# base.net
KiCad netlist of a schematic drawn in EAGLE
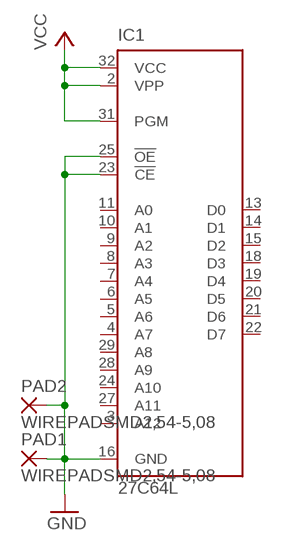
[diagram p0: schematic, sheet 1]

(export (version "E")
  (design (tool "Eeschema 10.0.6"))
  (components
    (comp (ref "IC1")
      (value "27C64L")
      (footprint "eagle-import:PLCC-32")
      (libsource (lib "eagle-import") (part "2764LC"))
    )
    (comp (ref "PAD1")
      (value "WIREPADSMD2,54-5,08")
      (footprint "eagle-import:SMD2,54-5,08")
      (libsource (lib "eagle-import") (part "WIREPADSMD2,54-5,08"))
    )
    (comp (ref "PAD2")
      (value "WIREPADSMD2,54-5,08")
      (footprint "eagle-import:SMD2,54-5,08")
      (libsource (lib "eagle-import") (part "WIREPADSMD2,54-5,08"))
    )
  )
  (nets
    (net (code "1") (name "GND") (class "Default")
      (node (ref "IC1") (pin "16") (pinfunction "GND_16") (pintype "power_in"))
      (node (ref "IC1") (pin "23") (pinfunction "~{CE}_23") (pintype "input"))
      (node (ref "IC1") (pin "25") (pinfunction "~{OE}_25") (pintype "input"))
      (node (ref "PAD1") (pin "1") (pinfunction "P_1") (pintype "passive"))
      (node (ref "PAD2") (pin "1") (pinfunction "P_1") (pintype "passive"))
    )
    (net (code "2") (name "VCC") (class "Default")
      (node (ref "IC1") (pin "2") (pinfunction "VPP_2") (pintype "input"))
      (node (ref "IC1") (pin "31") (pinfunction "PGM_31") (pintype "input"))
      (node (ref "IC1") (pin "32") (pinfunction "VCC_32") (pintype "power_in"))
    )
    (net (code "3") (name "unconnected-(IC1-A0-Pad11)") (class "Default")
      (node (ref "IC1") (pin "11") (pinfunction "A0_11") (pintype "input"))
    )
    (net (code "4") (name "unconnected-(IC1-A1-Pad10)") (class "Default")
      (node (ref "IC1") (pin "10") (pinfunction "A1_10") (pintype "input"))
    )
    (net (code "5") (name "unconnected-(IC1-A2-Pad9)") (class "Default")
      (node (ref "IC1") (pin "9") (pinfunction "A2_9") (pintype "input"))
    )
    (net (code "6") (name "unconnected-(IC1-A3-Pad8)") (class "Default")
      (node (ref "IC1") (pin "8") (pinfunction "A3_8") (pintype "input"))
    )
    (net (code "7") (name "unconnected-(IC1-A4-Pad7)") (class "Default")
      (node (ref "IC1") (pin "7") (pinfunction "A4_7") (pintype "input"))
    )
    (net (code "8") (name "unconnected-(IC1-A5-Pad6)") (class "Default")
      (node (ref "IC1") (pin "6") (pinfunction "A5_6") (pintype "input"))
    )
    (net (code "9") (name "unconnected-(IC1-A6-Pad5)") (class "Default")
      (node (ref "IC1") (pin "5") (pinfunction "A6_5") (pintype "input"))
    )
    (net (code "10") (name "unconnected-(IC1-A7-Pad4)") (class "Default")
      (node (ref "IC1") (pin "4") (pinfunction "A7_4") (pintype "input"))
    )
    (net (code "11") (name "unconnected-(IC1-A8-Pad29)") (class "Default")
      (node (ref "IC1") (pin "29") (pinfunction "A8_29") (pintype "input"))
    )
    (net (code "12") (name "unconnected-(IC1-A9-Pad28)") (class "Default")
      (node (ref "IC1") (pin "28") (pinfunction "A9_28") (pintype "input"))
    )
    (net (code "13") (name "unconnected-(IC1-A10-Pad24)") (class "Default")
      (node (ref "IC1") (pin "24") (pinfunction "A10_24") (pintype "input"))
    )
    (net (code "14") (name "unconnected-(IC1-A11-Pad27)") (class "Default")
      (node (ref "IC1") (pin "27") (pinfunction "A11_27") (pintype "input"))
    )
    (net (code "15") (name "unconnected-(IC1-A12-Pad3)") (class "Default")
      (node (ref "IC1") (pin "3") (pinfunction "A12_3") (pintype "input"))
    )
    (net (code "16") (name "unconnected-(IC1-D0-Pad13)") (class "Default")
      (node (ref "IC1") (pin "13") (pinfunction "D0_13") (pintype "tri_state"))
    )
    (net (code "17") (name "unconnected-(IC1-D1-Pad14)") (class "Default")
      (node (ref "IC1") (pin "14") (pinfunction "D1_14") (pintype "tri_state"))
    )
    (net (code "18") (name "unconnected-(IC1-D2-Pad15)") (class "Default")
      (node (ref "IC1") (pin "15") (pinfunction "D2_15") (pintype "tri_state"))
    )
    (net (code "19") (name "unconnected-(IC1-D3-Pad18)") (class "Default")
      (node (ref "IC1") (pin "18") (pinfunction "D3_18") (pintype "tri_state"))
    )
    (net (code "20") (name "unconnected-(IC1-D4-Pad19)") (class "Default")
      (node (ref "IC1") (pin "19") (pinfunction "D4_19") (pintype "tri_state"))
    )
    (net (code "21") (name "unconnected-(IC1-D5-Pad20)") (class "Default")
      (node (ref "IC1") (pin "20") (pinfunction "D5_20") (pintype "tri_state"))
    )
    (net (code "22") (name "unconnected-(IC1-D6-Pad21)") (class "Default")
      (node (ref "IC1") (pin "21") (pinfunction "D6_21") (pintype "tri_state"))
    )
    (net (code "23") (name "unconnected-(IC1-D7-Pad22)") (class "Default")
      (node (ref "IC1") (pin "22") (pinfunction "D7_22") (pintype "tri_state"))
    )
    (net (code "24") (name "unconnected-(IC1-NC-Pad1)") (class "Default")
      (node (ref "IC1") (pin "1") (pinfunction "NC_1") (pintype "no_connect"))
    )
  )
)
